# brainmachine.net
KiCad netlist of a schematic drawn in EAGLE
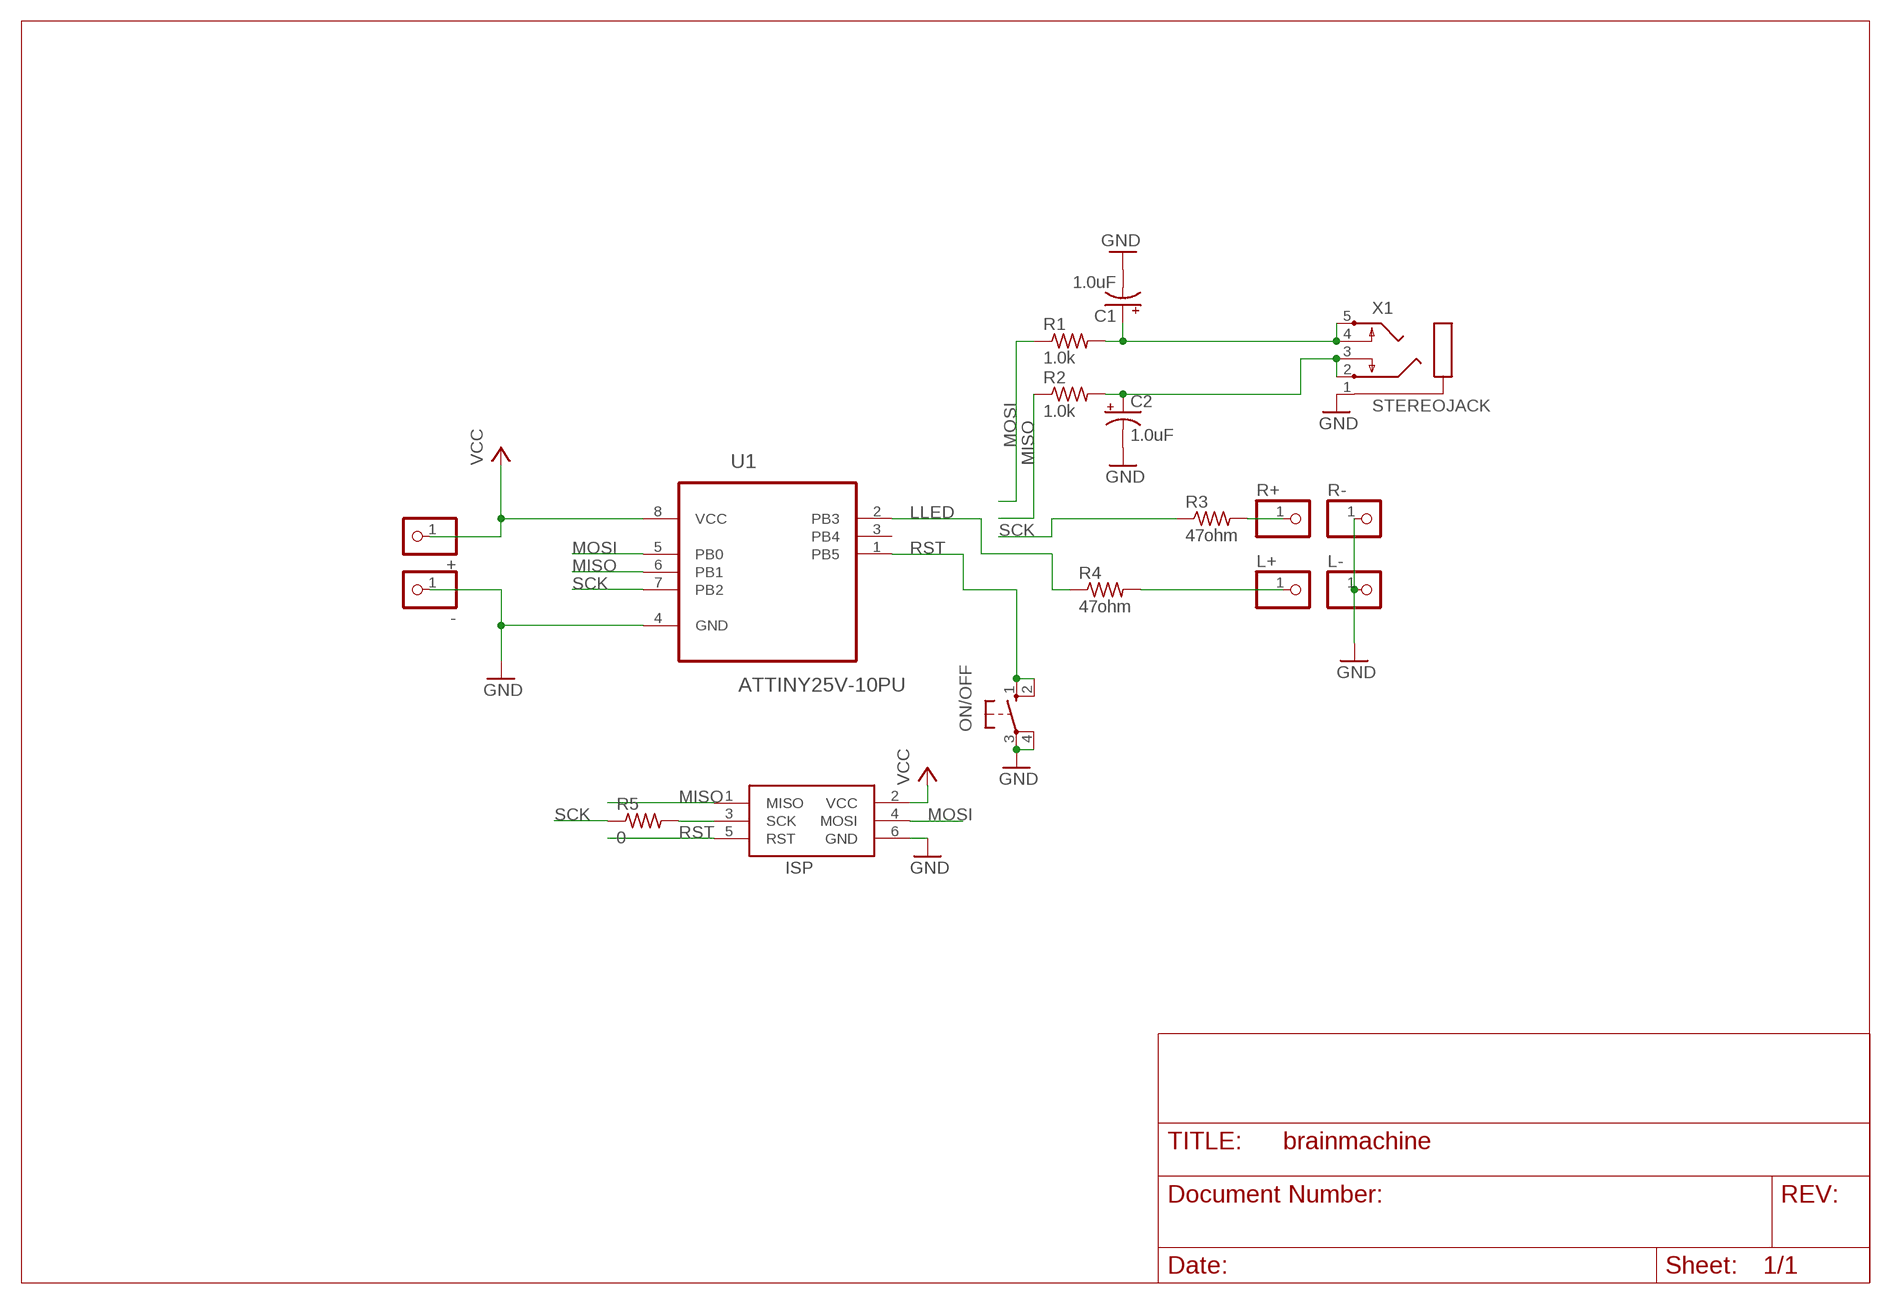
[diagram p0: schematic, sheet 1]

(export (version "E")
  (design (tool "Eeschema 10.0.6"))
  (components
    (comp (ref "+")
      (value "PINHD-1X1")
      (footprint "eagle-import:1X01")
      (libsource (lib "eagle-import") (part "PINHD-1X1"))
    )
    (comp (ref "-")
      (value "PINHD-1X1")
      (footprint "eagle-import:1X01")
      (libsource (lib "eagle-import") (part "PINHD-1X1"))
    )
    (comp (ref "C1")
      (value "1.0uF")
      (footprint "eagle-import:E2,5-5")
      (libsource (lib "eagle-import") (part "CPOL-USE2.5-5"))
    )
    (comp (ref "C2")
      (value "1.0uF")
      (footprint "eagle-import:E2,5-5")
      (libsource (lib "eagle-import") (part "CPOL-USE2.5-5"))
    )
    (comp (ref "ISP")
      (value "AVRISP-6")
      (footprint "eagle-import:AVRISP")
      (libsource (lib "eagle-import") (part "AVRISP-6"))
    )
    (comp (ref "L+")
      (value "PINHD-1X1")
      (footprint "eagle-import:1X01")
      (libsource (lib "eagle-import") (part "PINHD-1X1"))
    )
    (comp (ref "L-")
      (value "PINHD-1X1")
      (footprint "eagle-import:1X01")
      (libsource (lib "eagle-import") (part "PINHD-1X1"))
    )
    (comp (ref "ON/OFF")
      (value "10-XX")
      (footprint "eagle-import:B3F-10XX")
      (libsource (lib "eagle-import") (part "10-XX"))
    )
    (comp (ref "R+")
      (value "PINHD-1X1")
      (footprint "eagle-import:1X01")
      (libsource (lib "eagle-import") (part "PINHD-1X1"))
    )
    (comp (ref "R-")
      (value "PINHD-1X1")
      (footprint "eagle-import:1X01")
      (libsource (lib "eagle-import") (part "PINHD-1X1"))
    )
    (comp (ref "R1")
      (value "1.0k")
      (footprint "eagle-import:0207_10")
      (libsource (lib "eagle-import") (part "R-US_0207/10"))
    )
    (comp (ref "R2")
      (value "1.0k")
      (footprint "eagle-import:0207_10")
      (libsource (lib "eagle-import") (part "R-US_0207/10"))
    )
    (comp (ref "R3")
      (value "47ohm")
      (footprint "eagle-import:0207_10")
      (libsource (lib "eagle-import") (part "R-US_0207/10"))
    )
    (comp (ref "R4")
      (value "47ohm")
      (footprint "eagle-import:0207_10")
      (libsource (lib "eagle-import") (part "R-US_0207/10"))
    )
    (comp (ref "R5")
      (value "0")
      (footprint "eagle-import:0207_10")
      (libsource (lib "eagle-import") (part "R-US_0207/10"))
    )
    (comp (ref "U1")
      (value "ATTINY25V-10PU")
      (footprint "eagle-import:DIP254P762X533-8")
      (libsource (lib "eagle-import") (part "ATTINY25V-10PU"))
    )
    (comp (ref "X1")
      (value "STEREOJACK")
      (footprint "eagle-import:STX3100")
      (libsource (lib "eagle-import") (part "STEREOJACK"))
    )
  )
  (nets
    (net (code "1") (name "/LLED") (class "Default")
      (node (ref "R4") (pin "1") (pinfunction "1_1") (pintype "passive"))
      (node (ref "U1") (pin "2") (pinfunction "PB3_2") (pintype "bidirectional"))
    )
    (net (code "2") (name "/MISO") (class "Default")
      (node (ref "ISP") (pin "1") (pinfunction "MISO_1") (pintype "input"))
      (node (ref "R2") (pin "1") (pinfunction "1_1") (pintype "passive"))
      (node (ref "U1") (pin "6") (pinfunction "PB1_6") (pintype "bidirectional"))
    )
    (net (code "3") (name "/MOSI") (class "Default")
      (node (ref "ISP") (pin "4") (pinfunction "MOSI_4") (pintype "output"))
      (node (ref "R1") (pin "1") (pinfunction "1_1") (pintype "passive"))
      (node (ref "U1") (pin "5") (pinfunction "PB0_5") (pintype "bidirectional"))
    )
    (net (code "4") (name "/RST") (class "Default")
      (node (ref "ISP") (pin "5") (pinfunction "RST_5") (pintype "output"))
      (node (ref "ON/OFF") (pin "1") (pinfunction "S_1") (pintype "passive"))
      (node (ref "ON/OFF") (pin "2") (pinfunction "S1_2") (pintype "passive"))
      (node (ref "U1") (pin "1") (pinfunction "PB5_1") (pintype "bidirectional"))
    )
    (net (code "5") (name "/SCK") (class "Default")
      (node (ref "R3") (pin "1") (pinfunction "1_1") (pintype "passive"))
      (node (ref "R5") (pin "1") (pinfunction "1_1") (pintype "passive"))
      (node (ref "U1") (pin "7") (pinfunction "PB2_7") (pintype "bidirectional"))
    )
    (net (code "6") (name "GND") (class "Default")
      (node (ref "-") (pin "1") (pinfunction "1_1") (pintype "passive"))
      (node (ref "C1") (pin "-") (pinfunction "-_-") (pintype "passive"))
      (node (ref "C2") (pin "-") (pinfunction "-_-") (pintype "passive"))
      (node (ref "ISP") (pin "6") (pinfunction "GND_6") (pintype "power_in"))
      (node (ref "L-") (pin "1") (pinfunction "1_1") (pintype "passive"))
      (node (ref "ON/OFF") (pin "3") (pinfunction "P_3") (pintype "passive"))
      (node (ref "ON/OFF") (pin "4") (pinfunction "P1_4") (pintype "passive"))
      (node (ref "R-") (pin "1") (pinfunction "1_1") (pintype "passive"))
      (node (ref "U1") (pin "4") (pinfunction "GND_4") (pintype "passive"))
      (node (ref "X1") (pin "1") (pinfunction "1_1") (pintype "passive"))
    )
    (net (code "7") (name "Net-(C1-Pad+)") (class "Default")
      (node (ref "C1") (pin "+") (pinfunction "+_+") (pintype "passive"))
      (node (ref "R1") (pin "2") (pinfunction "2_2") (pintype "passive"))
      (node (ref "X1") (pin "4") (pinfunction "4_4") (pintype "passive"))
      (node (ref "X1") (pin "5") (pinfunction "5_5") (pintype "passive"))
    )
    (net (code "8") (name "Net-(C2-Pad+)") (class "Default")
      (node (ref "C2") (pin "+") (pinfunction "+_+") (pintype "passive"))
      (node (ref "R2") (pin "2") (pinfunction "2_2") (pintype "passive"))
      (node (ref "X1") (pin "2") (pinfunction "2_2") (pintype "passive"))
      (node (ref "X1") (pin "3") (pinfunction "3_3") (pintype "passive"))
    )
    (net (code "9") (name "Net-(ISP-SCK)") (class "Default")
      (node (ref "ISP") (pin "3") (pinfunction "SCK_3") (pintype "output"))
      (node (ref "R5") (pin "2") (pinfunction "2_2") (pintype "passive"))
    )
    (net (code "10") (name "Net-(L+-Pad1)") (class "Default")
      (node (ref "L+") (pin "1") (pinfunction "1_1") (pintype "passive"))
      (node (ref "R4") (pin "2") (pinfunction "2_2") (pintype "passive"))
    )
    (net (code "11") (name "Net-(R+-Pad1)") (class "Default")
      (node (ref "R+") (pin "1") (pinfunction "1_1") (pintype "passive"))
      (node (ref "R3") (pin "2") (pinfunction "2_2") (pintype "passive"))
    )
    (net (code "12") (name "VCC") (class "Default")
      (node (ref "+") (pin "1") (pinfunction "1_1") (pintype "passive"))
      (node (ref "ISP") (pin "2") (pinfunction "VCC_2") (pintype "power_in"))
      (node (ref "U1") (pin "8") (pinfunction "VCC_8") (pintype "power_in"))
    )
    (net (code "13") (name "unconnected-(U1-PB4-Pad3)") (class "Default")
      (node (ref "U1") (pin "3") (pinfunction "PB4_3") (pintype "bidirectional"))
    )
  )
)
